# HID2AMI_Deluxe_Rev1_0_0_redist.net
KiCad netlist of a schematic drawn in EAGLE
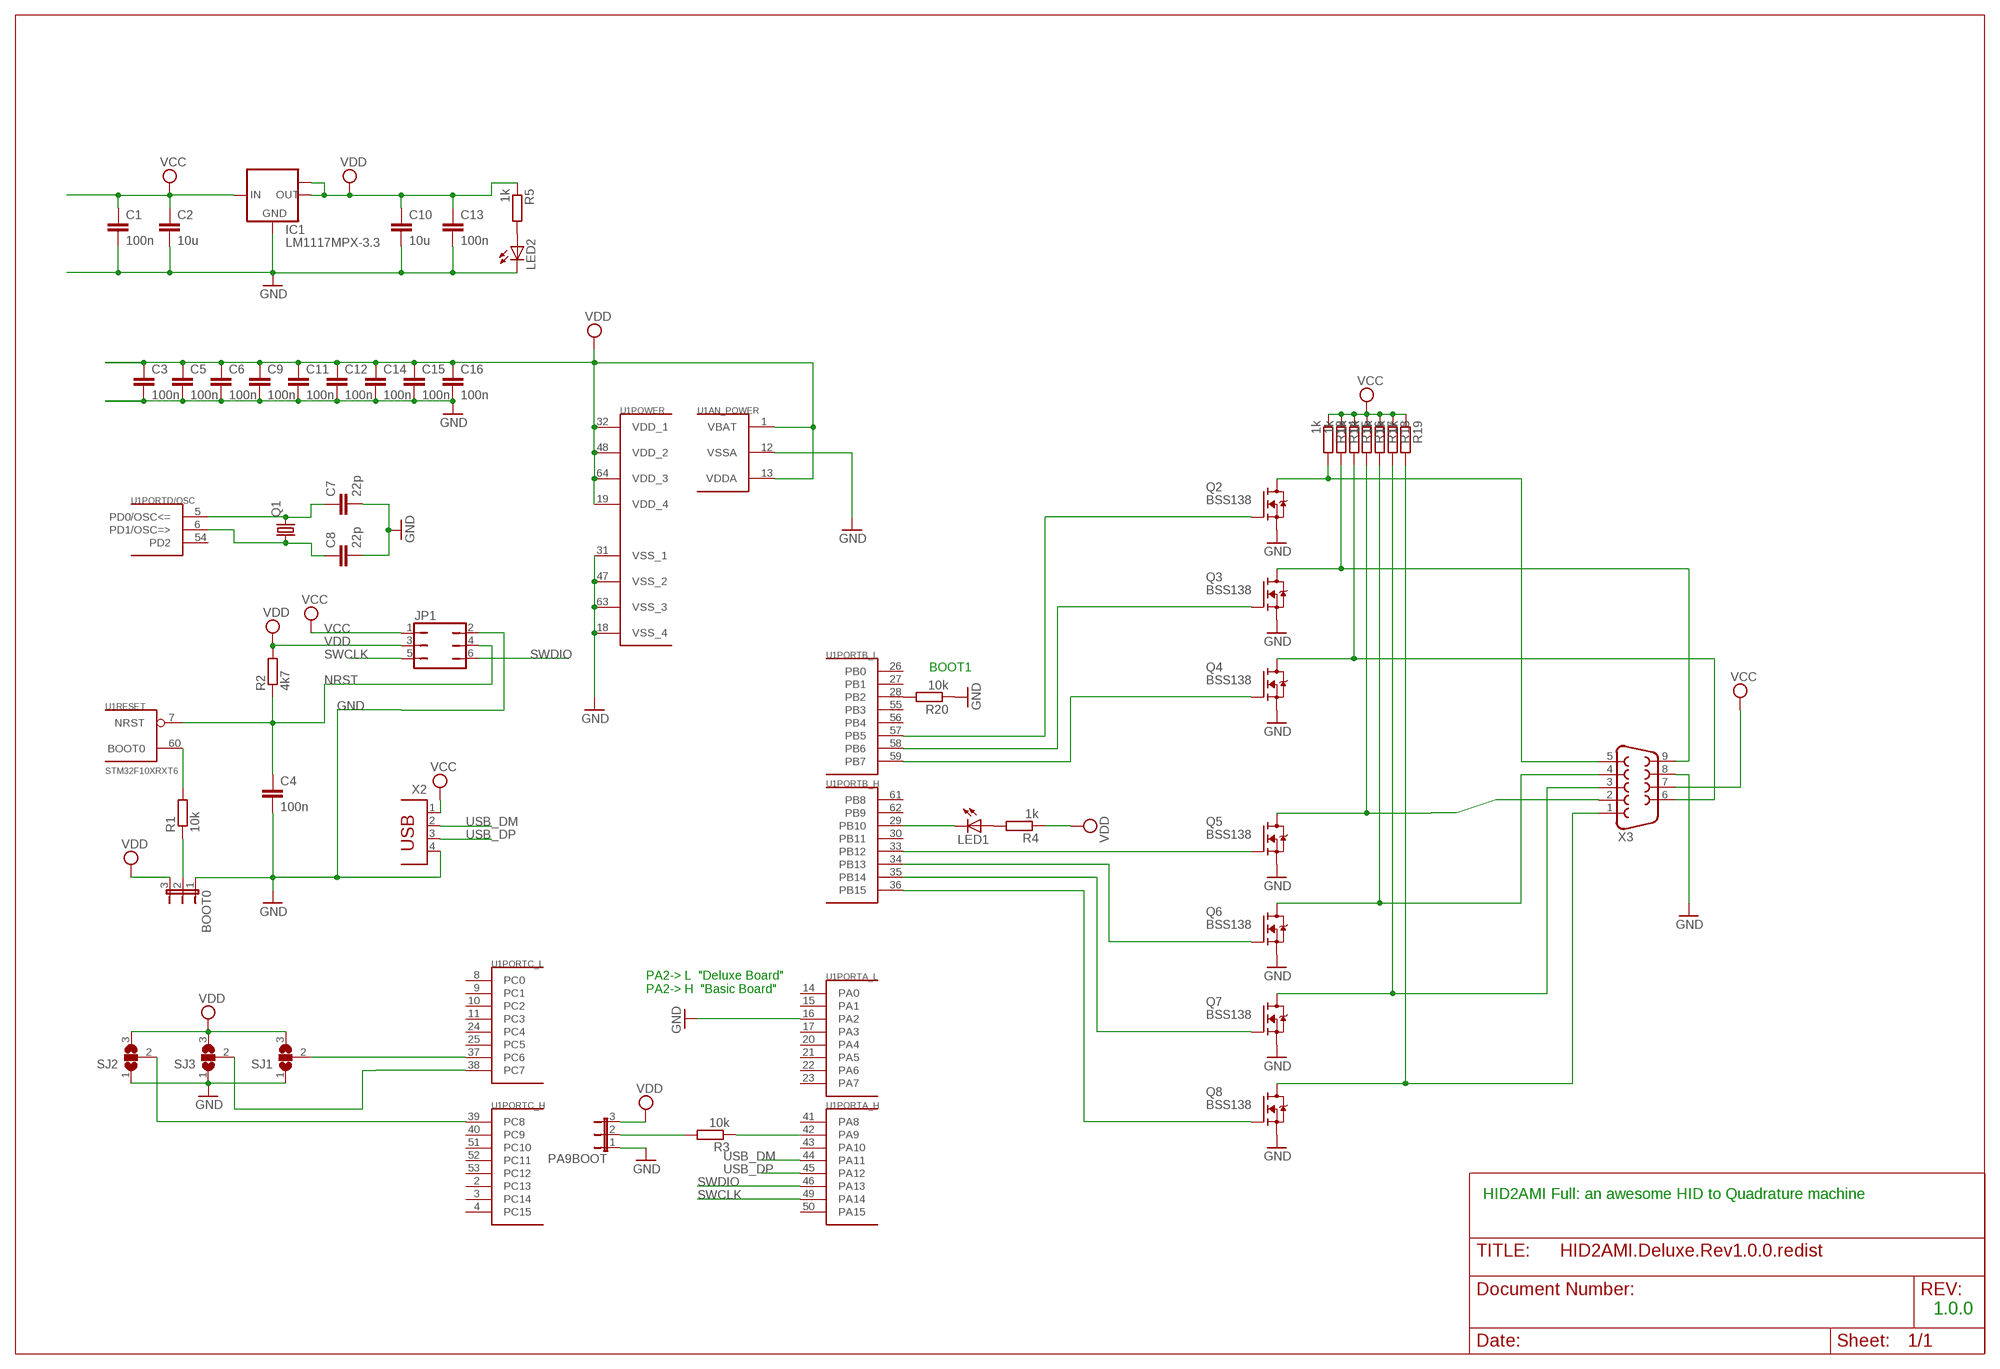
[diagram p0: schematic, sheet 1]

(export (version "E")
  (design (tool "Eeschema 10.0.6"))
  (components
    (comp (ref "BOOT0")
      (value "JP2E")
      (footprint "eagle-import:JP2")
      (libsource (lib "eagle-import") (part "JP2E"))
    )
    (comp (ref "C1")
      (value "100n")
      (footprint "eagle-import:C0805")
      (libsource (lib "eagle-import") (part "C-EUC0805"))
    )
    (comp (ref "C2")
      (value "10u")
      (footprint "eagle-import:C1206")
      (libsource (lib "eagle-import") (part "C-EUC1206"))
    )
    (comp (ref "C3")
      (value "100n")
      (footprint "eagle-import:C0805")
      (libsource (lib "eagle-import") (part "C-EUC0805"))
    )
    (comp (ref "C4")
      (value "100n")
      (footprint "eagle-import:C0805")
      (libsource (lib "eagle-import") (part "C-EUC0805"))
    )
    (comp (ref "C5")
      (value "100n")
      (footprint "eagle-import:C0805")
      (libsource (lib "eagle-import") (part "C-EUC0805"))
    )
    (comp (ref "C6")
      (value "100n")
      (footprint "eagle-import:C0805")
      (libsource (lib "eagle-import") (part "C-EUC0805"))
    )
    (comp (ref "C7")
      (value "22p")
      (footprint "eagle-import:C0805")
      (libsource (lib "eagle-import") (part "C-EUC0805"))
    )
    (comp (ref "C8")
      (value "22p")
      (footprint "eagle-import:C0805")
      (libsource (lib "eagle-import") (part "C-EUC0805"))
    )
    (comp (ref "C9")
      (value "100n")
      (footprint "eagle-import:C0805")
      (libsource (lib "eagle-import") (part "C-EUC0805"))
    )
    (comp (ref "C10")
      (value "10u")
      (footprint "eagle-import:C0805")
      (libsource (lib "eagle-import") (part "C-EUC0805"))
    )
    (comp (ref "C11")
      (value "100n")
      (footprint "eagle-import:C0805")
      (libsource (lib "eagle-import") (part "C-EUC0805"))
    )
    (comp (ref "C12")
      (value "100n")
      (footprint "eagle-import:C0805")
      (libsource (lib "eagle-import") (part "C-EUC0805"))
    )
    (comp (ref "C13")
      (value "100n")
      (footprint "eagle-import:C0805")
      (libsource (lib "eagle-import") (part "C-EUC0805"))
    )
    (comp (ref "C14")
      (value "100n")
      (footprint "eagle-import:C0805")
      (libsource (lib "eagle-import") (part "C-EUC0805"))
    )
    (comp (ref "C15")
      (value "100n")
      (footprint "eagle-import:C0805")
      (libsource (lib "eagle-import") (part "C-EUC0805"))
    )
    (comp (ref "C16")
      (value "100n")
      (footprint "eagle-import:C0805")
      (libsource (lib "eagle-import") (part "C-EUC0805"))
    )
    (comp (ref "IC1")
      (value "LM1117MPX-3.3")
      (footprint "eagle-import:SOT223")
      (libsource (lib "eagle-import") (part "LM1117MPX-3.3"))
    )
    (comp (ref "JP1")
      (value "JP3Q")
      (footprint "eagle-import:JP3Q")
      (libsource (lib "eagle-import") (part "JP3Q"))
    )
    (comp (ref "LED1")
      (value "LEDSML0805")
      (footprint "eagle-import:SML0805")
      (libsource (lib "eagle-import") (part "LEDSML0805"))
    )
    (comp (ref "LED2")
      (value "LEDSML0805")
      (footprint "eagle-import:SML0805")
      (libsource (lib "eagle-import") (part "LEDSML0805"))
    )
    (comp (ref "PA9BOOT")
      (value "JP2E")
      (footprint "eagle-import:JP2")
      (libsource (lib "eagle-import") (part "JP2E"))
    )
    (comp (ref "Q1")
      (value "CRYSTALHC49S")
      (footprint "eagle-import:HC49_S")
      (libsource (lib "eagle-import") (part "CRYSTALHC49S"))
    )
    (comp (ref "Q2")
      (value "BSS138")
      (footprint "eagle-import:SOT23")
      (fields (field (name "MF") "Fairchild"))
      (libsource (lib "eagle-import") (part "BSS138"))
    )
    (comp (ref "Q3")
      (value "BSS138")
      (footprint "eagle-import:SOT23")
      (fields (field (name "MF") "Fairchild"))
      (libsource (lib "eagle-import") (part "BSS138"))
    )
    (comp (ref "Q4")
      (value "BSS138")
      (footprint "eagle-import:SOT23")
      (fields (field (name "MF") "Fairchild"))
      (libsource (lib "eagle-import") (part "BSS138"))
    )
    (comp (ref "Q5")
      (value "BSS138")
      (footprint "eagle-import:SOT23")
      (fields (field (name "MF") "Fairchild"))
      (libsource (lib "eagle-import") (part "BSS138"))
    )
    (comp (ref "Q6")
      (value "BSS138")
      (footprint "eagle-import:SOT23")
      (fields (field (name "MF") "Fairchild"))
      (libsource (lib "eagle-import") (part "BSS138"))
    )
    (comp (ref "Q7")
      (value "BSS138")
      (footprint "eagle-import:SOT23")
      (fields (field (name "MF") "Fairchild"))
      (libsource (lib "eagle-import") (part "BSS138"))
    )
    (comp (ref "Q8")
      (value "BSS138")
      (footprint "eagle-import:SOT23")
      (fields (field (name "MF") "Fairchild"))
      (libsource (lib "eagle-import") (part "BSS138"))
    )
    (comp (ref "R1")
      (value "10k")
      (footprint "eagle-import:M0805")
      (libsource (lib "eagle-import") (part "R-EU_M0805"))
    )
    (comp (ref "R2")
      (value "4k7")
      (footprint "eagle-import:M0805")
      (libsource (lib "eagle-import") (part "R-EU_M0805"))
    )
    (comp (ref "R3")
      (value "10k")
      (footprint "eagle-import:M0805")
      (libsource (lib "eagle-import") (part "R-EU_M0805"))
    )
    (comp (ref "R4")
      (value "1k")
      (footprint "eagle-import:M0805")
      (libsource (lib "eagle-import") (part "R-EU_M0805"))
    )
    (comp (ref "R5")
      (value "1k")
      (footprint "eagle-import:M0805")
      (libsource (lib "eagle-import") (part "R-EU_M0805"))
    )
    (comp (ref "R13")
      (value "1k")
      (footprint "eagle-import:M0805")
      (libsource (lib "eagle-import") (part "R-EU_M0805"))
    )
    (comp (ref "R14")
      (value "1k")
      (footprint "eagle-import:M0805")
      (libsource (lib "eagle-import") (part "R-EU_M0805"))
    )
    (comp (ref "R15")
      (value "1k")
      (footprint "eagle-import:M0805")
      (libsource (lib "eagle-import") (part "R-EU_M0805"))
    )
    (comp (ref "R16")
      (value "1k")
      (footprint "eagle-import:M0805")
      (libsource (lib "eagle-import") (part "R-EU_M0805"))
    )
    (comp (ref "R17")
      (value "1k")
      (footprint "eagle-import:M0805")
      (libsource (lib "eagle-import") (part "R-EU_M0805"))
    )
    (comp (ref "R18")
      (value "1k")
      (footprint "eagle-import:M0805")
      (libsource (lib "eagle-import") (part "R-EU_M0805"))
    )
    (comp (ref "R19")
      (value "1k")
      (footprint "eagle-import:M0805")
      (libsource (lib "eagle-import") (part "R-EU_M0805"))
    )
    (comp (ref "R20")
      (value "10k")
      (footprint "eagle-import:M0805")
      (libsource (lib "eagle-import") (part "R-EU_M0805"))
    )
    (comp (ref "SJ1")
      (value "SJ2W")
      (footprint "eagle-import:SJ_2")
      (libsource (lib "eagle-import") (part "SJ2W"))
    )
    (comp (ref "SJ2")
      (value "SJ2W")
      (footprint "eagle-import:SJ_2")
      (libsource (lib "eagle-import") (part "SJ2W"))
    )
    (comp (ref "SJ3")
      (value "SJ2W")
      (footprint "eagle-import:SJ_2")
      (libsource (lib "eagle-import") (part "SJ2W"))
    )
    (comp (ref "U1")
      (value "STM32F10XRXT6")
      (footprint "eagle-import:TQFP64")
      (libsource (lib "eagle-import") (part "STM32F10XRXT6"))
    )
    (comp (ref "X2")
      (value "PN87520")
      (footprint "eagle-import:PN87520")
      (libsource (lib "eagle-import") (part "PN87520"))
    )
    (comp (ref "X3")
      (value "F09HP")
      (footprint "eagle-import:F09HP")
      (libsource (lib "eagle-import") (part "F09HP"))
    )
  )
  (nets
    (net (code "1") (name "/NRST") (class "Default")
      (node (ref "C4") (pin "1") (pinfunction "1_1") (pintype "passive"))
      (node (ref "JP1") (pin "4") (pinfunction "4_4") (pintype "passive"))
      (node (ref "R2") (pin "1") (pinfunction "1_1") (pintype "passive"))
      (node (ref "U1") (pin "7") (pinfunction "NRST_7") (pintype "input"))
    )
    (net (code "2") (name "/SWCLK") (class "Default")
      (node (ref "JP1") (pin "5") (pinfunction "5_5") (pintype "passive"))
      (node (ref "U1") (pin "49") (pinfunction "PA14_49") (pintype "bidirectional"))
    )
    (net (code "3") (name "/SWDIO") (class "Default")
      (node (ref "JP1") (pin "6") (pinfunction "6_6") (pintype "passive"))
      (node (ref "U1") (pin "46") (pinfunction "PA13_46") (pintype "bidirectional"))
    )
    (net (code "4") (name "/USB_DM") (class "Default")
      (node (ref "U1") (pin "44") (pinfunction "PA11_44") (pintype "bidirectional"))
      (node (ref "X2") (pin "2") (pinfunction "2_2") (pintype "passive"))
    )
    (net (code "5") (name "/USB_DP") (class "Default")
      (node (ref "U1") (pin "45") (pinfunction "PA12_45") (pintype "bidirectional"))
      (node (ref "X2") (pin "3") (pinfunction "3_3") (pintype "passive"))
    )
    (net (code "6") (name "GND") (class "Default")
      (node (ref "BOOT0") (pin "1") (pinfunction "1_1") (pintype "passive"))
      (node (ref "C1") (pin "2") (pinfunction "2_2") (pintype "passive"))
      (node (ref "C10") (pin "2") (pinfunction "2_2") (pintype "passive"))
      (node (ref "C11") (pin "2") (pinfunction "2_2") (pintype "passive"))
      (node (ref "C12") (pin "2") (pinfunction "2_2") (pintype "passive"))
      (node (ref "C13") (pin "2") (pinfunction "2_2") (pintype "passive"))
      (node (ref "C14") (pin "2") (pinfunction "2_2") (pintype "passive"))
      (node (ref "C15") (pin "2") (pinfunction "2_2") (pintype "passive"))
      (node (ref "C16") (pin "2") (pinfunction "2_2") (pintype "passive"))
      (node (ref "C2") (pin "2") (pinfunction "2_2") (pintype "passive"))
      (node (ref "C3") (pin "2") (pinfunction "2_2") (pintype "passive"))
      (node (ref "C4") (pin "2") (pinfunction "2_2") (pintype "passive"))
      (node (ref "C5") (pin "2") (pinfunction "2_2") (pintype "passive"))
      (node (ref "C6") (pin "2") (pinfunction "2_2") (pintype "passive"))
      (node (ref "C7") (pin "2") (pinfunction "2_2") (pintype "passive"))
      (node (ref "C8") (pin "2") (pinfunction "2_2") (pintype "passive"))
      (node (ref "C9") (pin "2") (pinfunction "2_2") (pintype "passive"))
      (node (ref "IC1") (pin "1") (pinfunction "GND_1") (pintype "input"))
      (node (ref "JP1") (pin "2") (pinfunction "2_2") (pintype "passive"))
      (node (ref "LED2") (pin "C") (pinfunction "C_C") (pintype "passive"))
      (node (ref "PA9BOOT") (pin "1") (pinfunction "1_1") (pintype "passive"))
      (node (ref "Q2") (pin "2") (pinfunction "S_2") (pintype "passive"))
      (node (ref "Q3") (pin "2") (pinfunction "S_2") (pintype "passive"))
      (node (ref "Q4") (pin "2") (pinfunction "S_2") (pintype "passive"))
      (node (ref "Q5") (pin "2") (pinfunction "S_2") (pintype "passive"))
      (node (ref "Q6") (pin "2") (pinfunction "S_2") (pintype "passive"))
      (node (ref "Q7") (pin "2") (pinfunction "S_2") (pintype "passive"))
      (node (ref "Q8") (pin "2") (pinfunction "S_2") (pintype "passive"))
      (node (ref "R20") (pin "1") (pinfunction "1_1") (pintype "passive"))
      (node (ref "SJ1") (pin "1") (pinfunction "1_1") (pintype "passive"))
      (node (ref "SJ2") (pin "1") (pinfunction "1_1") (pintype "passive"))
      (node (ref "SJ3") (pin "1") (pinfunction "1_1") (pintype "passive"))
      (node (ref "U1") (pin "12") (pinfunction "VSSA_12") (pintype "power_in"))
      (node (ref "U1") (pin "16") (pinfunction "PA2_16") (pintype "bidirectional"))
      (node (ref "U1") (pin "18") (pinfunction "VSS_4_18") (pintype "power_in"))
      (node (ref "U1") (pin "31") (pinfunction "VSS_1_31") (pintype "power_in"))
      (node (ref "U1") (pin "47") (pinfunction "VSS_2_47") (pintype "power_in"))
      (node (ref "U1") (pin "63") (pinfunction "VSS_3_63") (pintype "power_in"))
      (node (ref "X2") (pin "4") (pinfunction "4_4") (pintype "passive"))
      (node (ref "X3") (pin "8") (pinfunction "8_8") (pintype "passive"))
    )
    (net (code "7") (name "Net-(BOOT0-Pad2)") (class "Default")
      (node (ref "BOOT0") (pin "2") (pinfunction "2_2") (pintype "passive"))
      (node (ref "R1") (pin "1") (pinfunction "1_1") (pintype "passive"))
    )
    (net (code "8") (name "Net-(LED1-PadA)") (class "Default")
      (node (ref "LED1") (pin "A") (pinfunction "A_A") (pintype "passive"))
      (node (ref "R4") (pin "2") (pinfunction "2_2") (pintype "passive"))
    )
    (net (code "9") (name "Net-(LED2-PadA)") (class "Default")
      (node (ref "LED2") (pin "A") (pinfunction "A_A") (pintype "passive"))
      (node (ref "R5") (pin "2") (pinfunction "2_2") (pintype "passive"))
    )
    (net (code "10") (name "Net-(PA9BOOT-Pad2)") (class "Default")
      (node (ref "PA9BOOT") (pin "2") (pinfunction "2_2") (pintype "passive"))
      (node (ref "R3") (pin "2") (pinfunction "2_2") (pintype "passive"))
    )
    (net (code "11") (name "Net-(Q2-D)") (class "Default")
      (node (ref "Q2") (pin "3") (pinfunction "D_3") (pintype "passive"))
      (node (ref "R13") (pin "2") (pinfunction "2_2") (pintype "passive"))
      (node (ref "X3") (pin "5") (pinfunction "5_5") (pintype "passive"))
    )
    (net (code "12") (name "Net-(Q2-G)") (class "Default")
      (node (ref "Q2") (pin "1") (pinfunction "G_1") (pintype "passive"))
      (node (ref "U1") (pin "57") (pinfunction "PB5_57") (pintype "bidirectional"))
    )
    (net (code "13") (name "Net-(Q3-D)") (class "Default")
      (node (ref "Q3") (pin "3") (pinfunction "D_3") (pintype "passive"))
      (node (ref "R14") (pin "2") (pinfunction "2_2") (pintype "passive"))
      (node (ref "X3") (pin "9") (pinfunction "9_9") (pintype "passive"))
    )
    (net (code "14") (name "Net-(Q3-G)") (class "Default")
      (node (ref "Q3") (pin "1") (pinfunction "G_1") (pintype "passive"))
      (node (ref "U1") (pin "58") (pinfunction "PB6_58") (pintype "bidirectional"))
    )
    (net (code "15") (name "Net-(Q4-D)") (class "Default")
      (node (ref "Q4") (pin "3") (pinfunction "D_3") (pintype "passive"))
      (node (ref "R15") (pin "2") (pinfunction "2_2") (pintype "passive"))
      (node (ref "X3") (pin "6") (pinfunction "6_6") (pintype "passive"))
    )
    (net (code "16") (name "Net-(Q4-G)") (class "Default")
      (node (ref "Q4") (pin "1") (pinfunction "G_1") (pintype "passive"))
      (node (ref "U1") (pin "59") (pinfunction "PB7_59") (pintype "bidirectional"))
    )
    (net (code "17") (name "Net-(Q5-D)") (class "Default")
      (node (ref "Q5") (pin "3") (pinfunction "D_3") (pintype "passive"))
      (node (ref "R16") (pin "2") (pinfunction "2_2") (pintype "passive"))
      (node (ref "X3") (pin "2") (pinfunction "2_2") (pintype "passive"))
    )
    (net (code "18") (name "Net-(Q5-G)") (class "Default")
      (node (ref "Q5") (pin "1") (pinfunction "G_1") (pintype "passive"))
      (node (ref "U1") (pin "33") (pinfunction "PB12_33") (pintype "bidirectional"))
    )
    (net (code "19") (name "Net-(Q6-D)") (class "Default")
      (node (ref "Q6") (pin "3") (pinfunction "D_3") (pintype "passive"))
      (node (ref "R17") (pin "2") (pinfunction "2_2") (pintype "passive"))
      (node (ref "X3") (pin "4") (pinfunction "4_4") (pintype "passive"))
    )
    (net (code "20") (name "Net-(Q6-G)") (class "Default")
      (node (ref "Q6") (pin "1") (pinfunction "G_1") (pintype "passive"))
      (node (ref "U1") (pin "34") (pinfunction "PB13_34") (pintype "bidirectional"))
    )
    (net (code "21") (name "Net-(Q7-D)") (class "Default")
      (node (ref "Q7") (pin "3") (pinfunction "D_3") (pintype "passive"))
      (node (ref "R18") (pin "2") (pinfunction "2_2") (pintype "passive"))
      (node (ref "X3") (pin "3") (pinfunction "3_3") (pintype "passive"))
    )
    (net (code "22") (name "Net-(Q7-G)") (class "Default")
      (node (ref "Q7") (pin "1") (pinfunction "G_1") (pintype "passive"))
      (node (ref "U1") (pin "35") (pinfunction "PB14_35") (pintype "bidirectional"))
    )
    (net (code "23") (name "Net-(Q8-D)") (class "Default")
      (node (ref "Q8") (pin "3") (pinfunction "D_3") (pintype "passive"))
      (node (ref "R19") (pin "2") (pinfunction "2_2") (pintype "passive"))
      (node (ref "X3") (pin "1") (pinfunction "1_1") (pintype "passive"))
    )
    (net (code "24") (name "Net-(Q8-G)") (class "Default")
      (node (ref "Q8") (pin "1") (pinfunction "G_1") (pintype "passive"))
      (node (ref "U1") (pin "36") (pinfunction "PB15_36") (pintype "bidirectional"))
    )
    (net (code "25") (name "Net-(U1B-PA9)") (class "Default")
      (node (ref "R3") (pin "1") (pinfunction "1_1") (pintype "passive"))
      (node (ref "U1") (pin "42") (pinfunction "PA9_42") (pintype "bidirectional"))
    )
    (net (code "26") (name "Net-(U1D-PB10)") (class "Default")
      (node (ref "LED1") (pin "C") (pinfunction "C_C") (pintype "passive"))
      (node (ref "U1") (pin "29") (pinfunction "PB10_29") (pintype "bidirectional"))
    )
    (net (code "27") (name "Net-(U1E-PB2)") (class "Default")
      (node (ref "R20") (pin "2") (pinfunction "2_2") (pintype "passive"))
      (node (ref "U1") (pin "28") (pinfunction "PB2_28") (pintype "bidirectional"))
    )
    (net (code "28") (name "Net-(U1F-PC8)") (class "Default")
      (node (ref "SJ2") (pin "2") (pinfunction "2_2") (pintype "passive"))
      (node (ref "U1") (pin "39") (pinfunction "PC8_39") (pintype "bidirectional"))
    )
    (net (code "29") (name "Net-(U1G-PC6)") (class "Default")
      (node (ref "SJ1") (pin "2") (pinfunction "2_2") (pintype "passive"))
      (node (ref "U1") (pin "37") (pinfunction "PC6_37") (pintype "bidirectional"))
    )
    (net (code "30") (name "Net-(U1G-PC7)") (class "Default")
      (node (ref "SJ3") (pin "2") (pinfunction "2_2") (pintype "passive"))
      (node (ref "U1") (pin "38") (pinfunction "PC7_38") (pintype "bidirectional"))
    )
    (net (code "31") (name "Net-(U1H-PD0{slash}OSC<=)") (class "Default")
      (node (ref "C7") (pin "1") (pinfunction "1_1") (pintype "passive"))
      (node (ref "Q1") (pin "2") (pinfunction "2_2") (pintype "passive"))
      (node (ref "U1") (pin "5") (pinfunction "PD0/OSC<=_5") (pintype "bidirectional"))
    )
    (net (code "32") (name "Net-(U1H-PD1{slash}OSC=>)") (class "Default")
      (node (ref "C8") (pin "1") (pinfunction "1_1") (pintype "passive"))
      (node (ref "Q1") (pin "1") (pinfunction "1_1") (pintype "passive"))
      (node (ref "U1") (pin "6") (pinfunction "PD1/OSC=>_6") (pintype "bidirectional"))
    )
    (net (code "33") (name "Net-(U1J-BOOT0)") (class "Default")
      (node (ref "R1") (pin "2") (pinfunction "2_2") (pintype "passive"))
      (node (ref "U1") (pin "60") (pinfunction "BOOT0_60") (pintype "input"))
    )
    (net (code "34") (name "VCC") (class "Default")
      (node (ref "C1") (pin "1") (pinfunction "1_1") (pintype "passive"))
      (node (ref "C2") (pin "1") (pinfunction "1_1") (pintype "passive"))
      (node (ref "IC1") (pin "3") (pinfunction "IN_3") (pintype "input"))
      (node (ref "JP1") (pin "1") (pinfunction "1_1") (pintype "passive"))
      (node (ref "R13") (pin "1") (pinfunction "1_1") (pintype "passive"))
      (node (ref "R14") (pin "1") (pinfunction "1_1") (pintype "passive"))
      (node (ref "R15") (pin "1") (pinfunction "1_1") (pintype "passive"))
      (node (ref "R16") (pin "1") (pinfunction "1_1") (pintype "passive"))
      (node (ref "R17") (pin "1") (pinfunction "1_1") (pintype "passive"))
      (node (ref "R18") (pin "1") (pinfunction "1_1") (pintype "passive"))
      (node (ref "R19") (pin "1") (pinfunction "1_1") (pintype "passive"))
      (node (ref "X2") (pin "1") (pinfunction "1_1") (pintype "passive"))
      (node (ref "X3") (pin "7") (pinfunction "7_7") (pintype "passive"))
    )
    (net (code "35") (name "VDD") (class "Default")
      (node (ref "BOOT0") (pin "3") (pinfunction "3_3") (pintype "passive"))
      (node (ref "C10") (pin "1") (pinfunction "1_1") (pintype "passive"))
      (node (ref "C11") (pin "1") (pinfunction "1_1") (pintype "passive"))
      (node (ref "C12") (pin "1") (pinfunction "1_1") (pintype "passive"))
      (node (ref "C13") (pin "1") (pinfunction "1_1") (pintype "passive"))
      (node (ref "C14") (pin "1") (pinfunction "1_1") (pintype "passive"))
      (node (ref "C15") (pin "1") (pinfunction "1_1") (pintype "passive"))
      (node (ref "C16") (pin "1") (pinfunction "1_1") (pintype "passive"))
      (node (ref "C3") (pin "1") (pinfunction "1_1") (pintype "passive"))
      (node (ref "C5") (pin "1") (pinfunction "1_1") (pintype "passive"))
      (node (ref "C6") (pin "1") (pinfunction "1_1") (pintype "passive"))
      (node (ref "C9") (pin "1") (pinfunction "1_1") (pintype "passive"))
      (node (ref "IC1") (pin "2") (pinfunction "OUT_2") (pintype "passive"))
      (node (ref "IC1") (pin "TAB") (pinfunction "OUT1_TAB") (pintype "passive"))
      (node (ref "JP1") (pin "3") (pinfunction "3_3") (pintype "passive"))
      (node (ref "PA9BOOT") (pin "3") (pinfunction "3_3") (pintype "passive"))
      (node (ref "R2") (pin "2") (pinfunction "2_2") (pintype "passive"))
      (node (ref "R4") (pin "1") (pinfunction "1_1") (pintype "passive"))
      (node (ref "R5") (pin "1") (pinfunction "1_1") (pintype "passive"))
      (node (ref "SJ1") (pin "3") (pinfunction "3_3") (pintype "passive"))
      (node (ref "SJ2") (pin "3") (pinfunction "3_3") (pintype "passive"))
      (node (ref "SJ3") (pin "3") (pinfunction "3_3") (pintype "passive"))
      (node (ref "U1") (pin "1") (pinfunction "VBAT_1") (pintype "power_in"))
      (node (ref "U1") (pin "13") (pinfunction "VDDA_13") (pintype "power_in"))
      (node (ref "U1") (pin "19") (pinfunction "VDD_4_19") (pintype "power_in"))
      (node (ref "U1") (pin "32") (pinfunction "VDD_1_32") (pintype "power_in"))
      (node (ref "U1") (pin "48") (pinfunction "VDD_2_48") (pintype "power_in"))
      (node (ref "U1") (pin "64") (pinfunction "VDD_3_64") (pintype "power_in"))
    )
    (net (code "36") (name "unconnected-(U1B-PA8-Pad41)") (class "Default")
      (node (ref "U1") (pin "41") (pinfunction "PA8_41") (pintype "bidirectional"))
    )
    (net (code "37") (name "unconnected-(U1B-PA10-Pad43)") (class "Default")
      (node (ref "U1") (pin "43") (pinfunction "PA10_43") (pintype "bidirectional"))
    )
    (net (code "38") (name "unconnected-(U1B-PA15-Pad50)") (class "Default")
      (node (ref "U1") (pin "50") (pinfunction "PA15_50") (pintype "bidirectional"))
    )
    (net (code "39") (name "unconnected-(U1C-PA0-Pad14)") (class "Default")
      (node (ref "U1") (pin "14") (pinfunction "PA0_14") (pintype "bidirectional"))
    )
    (net (code "40") (name "unconnected-(U1C-PA1-Pad15)") (class "Default")
      (node (ref "U1") (pin "15") (pinfunction "PA1_15") (pintype "bidirectional"))
    )
    (net (code "41") (name "unconnected-(U1C-PA3-Pad17)") (class "Default")
      (node (ref "U1") (pin "17") (pinfunction "PA3_17") (pintype "bidirectional"))
    )
    (net (code "42") (name "unconnected-(U1C-PA4-Pad20)") (class "Default")
      (node (ref "U1") (pin "20") (pinfunction "PA4_20") (pintype "bidirectional"))
    )
    (net (code "43") (name "unconnected-(U1C-PA5-Pad21)") (class "Default")
      (node (ref "U1") (pin "21") (pinfunction "PA5_21") (pintype "bidirectional"))
    )
    (net (code "44") (name "unconnected-(U1C-PA6-Pad22)") (class "Default")
      (node (ref "U1") (pin "22") (pinfunction "PA6_22") (pintype "bidirectional"))
    )
    (net (code "45") (name "unconnected-(U1C-PA7-Pad23)") (class "Default")
      (node (ref "U1") (pin "23") (pinfunction "PA7_23") (pintype "bidirectional"))
    )
    (net (code "46") (name "unconnected-(U1D-PB8-Pad61)") (class "Default")
      (node (ref "U1") (pin "61") (pinfunction "PB8_61") (pintype "bidirectional"))
    )
    (net (code "47") (name "unconnected-(U1D-PB9-Pad62)") (class "Default")
      (node (ref "U1") (pin "62") (pinfunction "PB9_62") (pintype "bidirectional"))
    )
    (net (code "48") (name "unconnected-(U1D-PB11-Pad30)") (class "Default")
      (node (ref "U1") (pin "30") (pinfunction "PB11_30") (pintype "bidirectional"))
    )
    (net (code "49") (name "unconnected-(U1E-PB0-Pad26)") (class "Default")
      (node (ref "U1") (pin "26") (pinfunction "PB0_26") (pintype "bidirectional"))
    )
    (net (code "50") (name "unconnected-(U1E-PB1-Pad27)") (class "Default")
      (node (ref "U1") (pin "27") (pinfunction "PB1_27") (pintype "bidirectional"))
    )
    (net (code "51") (name "unconnected-(U1E-PB3-Pad55)") (class "Default")
      (node (ref "U1") (pin "55") (pinfunction "PB3_55") (pintype "bidirectional"))
    )
    (net (code "52") (name "unconnected-(U1E-PB4-Pad56)") (class "Default")
      (node (ref "U1") (pin "56") (pinfunction "PB4_56") (pintype "bidirectional"))
    )
    (net (code "53") (name "unconnected-(U1F-PC9-Pad40)") (class "Default")
      (node (ref "U1") (pin "40") (pinfunction "PC9_40") (pintype "bidirectional"))
    )
    (net (code "54") (name "unconnected-(U1F-PC10-Pad51)") (class "Default")
      (node (ref "U1") (pin "51") (pinfunction "PC10_51") (pintype "bidirectional"))
    )
    (net (code "55") (name "unconnected-(U1F-PC11-Pad52)") (class "Default")
      (node (ref "U1") (pin "52") (pinfunction "PC11_52") (pintype "bidirectional"))
    )
    (net (code "56") (name "unconnected-(U1F-PC12-Pad53)") (class "Default")
      (node (ref "U1") (pin "53") (pinfunction "PC12_53") (pintype "bidirectional"))
    )
    (net (code "57") (name "unconnected-(U1F-PC13-Pad2)") (class "Default")
      (node (ref "U1") (pin "2") (pinfunction "PC13_2") (pintype "bidirectional"))
    )
    (net (code "58") (name "unconnected-(U1F-PC14-Pad3)") (class "Default")
      (node (ref "U1") (pin "3") (pinfunction "PC14_3") (pintype "bidirectional"))
    )
    (net (code "59") (name "unconnected-(U1F-PC15-Pad4)") (class "Default")
      (node (ref "U1") (pin "4") (pinfunction "PC15_4") (pintype "bidirectional"))
    )
    (net (code "60") (name "unconnected-(U1G-PC0-Pad8)") (class "Default")
      (node (ref "U1") (pin "8") (pinfunction "PC0_8") (pintype "bidirectional"))
    )
    (net (code "61") (name "unconnected-(U1G-PC1-Pad9)") (class "Default")
      (node (ref "U1") (pin "9") (pinfunction "PC1_9") (pintype "bidirectional"))
    )
    (net (code "62") (name "unconnected-(U1G-PC2-Pad10)") (class "Default")
      (node (ref "U1") (pin "10") (pinfunction "PC2_10") (pintype "bidirectional"))
    )
    (net (code "63") (name "unconnected-(U1G-PC3-Pad11)") (class "Default")
      (node (ref "U1") (pin "11") (pinfunction "PC3_11") (pintype "bidirectional"))
    )
    (net (code "64") (name "unconnected-(U1G-PC4-Pad24)") (class "Default")
      (node (ref "U1") (pin "24") (pinfunction "PC4_24") (pintype "bidirectional"))
    )
    (net (code "65") (name "unconnected-(U1G-PC5-Pad25)") (class "Default")
      (node (ref "U1") (pin "25") (pinfunction "PC5_25") (pintype "bidirectional"))
    )
    (net (code "66") (name "unconnected-(U1H-PD2-Pad54)") (class "Default")
      (node (ref "U1") (pin "54") (pinfunction "PD2_54") (pintype "bidirectional"))
    )
  )
)
